# pca10100_sheet3_pin_map.net
KiCad netlist of a schematic drawn in Altium Designer
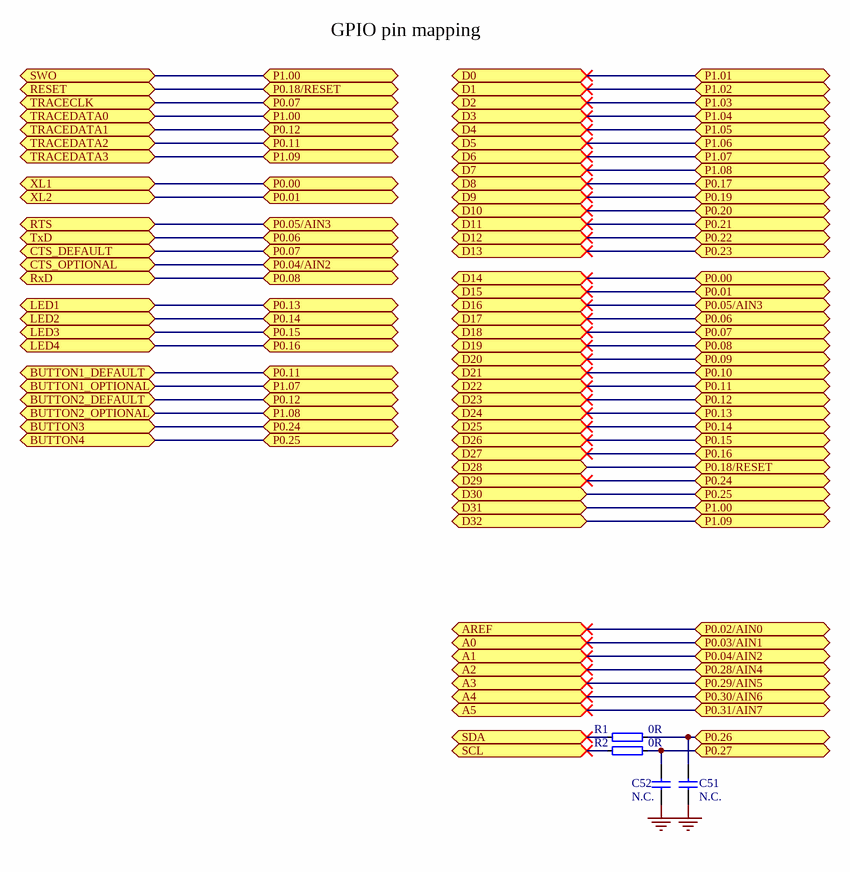
[diagram p0: pca10100_sheet3_pin_map.SchDoc]

(export (version "E")
  (design (tool "Eeschema 10.0.6"))
  (components
    (comp (ref "C51")
      (value "N.C.")
      (footprint "CAPC0603X03L_C_NC")
      (description "Not mounted")
      (fields (field (name "PART NUMBER") "C0201-N.C.") (field (name "MANUFACTURER") "N.A."))
      (libsource (lib "AltiumLib") (part "CAP"))
    )
    (comp (ref "C52")
      (value "N.C.")
      (footprint "CAPC0603X03L_C_NC")
      (description "Not mounted")
      (fields (field (name "PART NUMBER") "C0201-N.C.") (field (name "MANUFACTURER") "N.A."))
      (libsource (lib "AltiumLib") (part "CAP"))
    )
    (comp (ref "R1")
      (value "0R")
      (footprint "RESC0603X03L_C")
      (description "Resistor, ±5%, 0.05W")
      (fields (field (name "PART NUMBER") "R0201-0R") (field (name "MANUFACTURER") "N.A."))
      (libsource (lib "AltiumLib") (part "RES"))
    )
    (comp (ref "R2")
      (value "0R")
      (footprint "RESC0603X03L_C")
      (description "Resistor, ±5%, 0.05W")
      (fields (field (name "PART NUMBER") "R0201-0R") (field (name "MANUFACTURER") "N.A."))
      (libsource (lib "AltiumLib") (part "RES"))
    )
  )
  (nets
    (net (code "41") (name "/P0.26") (class "Default")
      (node (ref "C51") (pin "2") (pinfunction "2_2") (pintype "passive"))
      (node (ref "R1") (pin "2") (pinfunction "2_2") (pintype "passive"))
    )
    (net (code "42") (name "/P0.27") (class "Default")
      (node (ref "C52") (pin "1") (pinfunction "1_1") (pintype "passive"))
      (node (ref "R2") (pin "2") (pinfunction "2_2") (pintype "passive"))
    )
    (net (code "43") (name "/SCL") (class "Default")
      (node (ref "R2") (pin "1") (pinfunction "1_1") (pintype "passive+no_connect"))
    )
    (net (code "44") (name "/SDA") (class "Default")
      (node (ref "R1") (pin "1") (pinfunction "1_1") (pintype "passive+no_connect"))
    )
    (net (code "45") (name "GND") (class "Default")
      (node (ref "C51") (pin "1") (pinfunction "1_1") (pintype "passive"))
      (node (ref "C52") (pin "2") (pinfunction "2_2") (pintype "passive"))
    )
  )
)
